# DWM1000_Base.net
KiCad netlist of a schematic drawn in Altium Designer
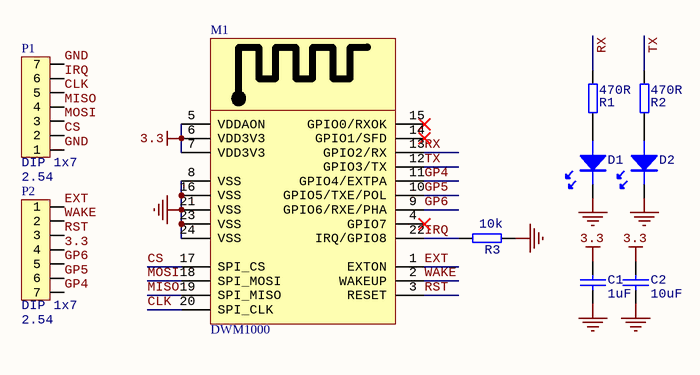
[diagram p0: DWM1000 Base.SchDoc]

(export (version "E")
  (design (tool "Eeschema 10.0.6"))
  (components
    (comp (ref "C1") (value "1uF") (footprint "0603C") (libsource (lib "HH_Lib_A") (part "CAP")))
    (comp (ref "C2") (value "10uF") (footprint "0603C") (libsource (lib "HH_Lib_A") (part "CAP")))
    (comp (ref "D1") (value "LED") (footprint "LED_0805B") (libsource (lib "HH_Lib_A") (part "LED")))
    (comp (ref "D2") (value "LED") (footprint "LED_0805R") (libsource (lib "HH_Lib_A") (part "LED")))
    (comp (ref "M1")
      (value "DWM1000")
      (footprint "HH_Pcb_B:DWM1000")
      (description "Module")
      (fields (field (name "MANUFACTURER") "Decawave Limited"))
      (libsource (lib "HH_Lib_B") (part "DWM1000"))
    )
    (comp (ref "P1")
      (value "2.54")
      (footprint "HDR1X7_2.54_180")
      (description "Header")
      (fields (field (name "TYPE") "DIP 1x7") (field (name "Comment") "DIP 1x7"))
      (libsource (lib "") (part "2.54MM_7P_1"))
    )
    (comp (ref "P2")
      (value "2.54")
      (footprint "HDR1X7_2.54_180")
      (description "Header")
      (fields (field (name "TYPE") "DIP 1x7") (field (name "Comment") "DIP 1x7"))
      (libsource (lib "HH_Lib_C") (part "2.54MM_7P"))
    )
    (comp (ref "R1") (value "470R") (footprint "0603R") (libsource (lib "HH_Lib_A") (part "RES")))
    (comp (ref "R2") (value "470R") (footprint "0603R") (libsource (lib "HH_Lib_A") (part "RES")))
    (comp (ref "R3") (value "10k") (footprint "0603R") (libsource (lib "HH_Lib_A") (part "RES")))
  )
  (nets
    (net (code "1") (name "/CLK") (class "Default")
      (node (ref "M1") (pin "20") (pinfunction "SPI_CLK_20") (pintype "passive"))
      (node (ref "P1") (pin "5") (pinfunction "5_5") (pintype "passive"))
    )
    (net (code "2") (name "/CS") (class "Default")
      (node (ref "M1") (pin "17") (pinfunction "SPI_CS_17") (pintype "passive"))
      (node (ref "P1") (pin "2") (pinfunction "2_2") (pintype "passive"))
    )
    (net (code "3") (name "/EXT") (class "Default")
      (node (ref "M1") (pin "1") (pinfunction "EXTON_1") (pintype "passive"))
      (node (ref "P2") (pin "1") (pinfunction "1_1") (pintype "passive"))
    )
    (net (code "4") (name "/GP4") (class "Default")
      (node (ref "M1") (pin "11") (pinfunction "GPIO4/EXTPA_11") (pintype "passive"))
      (node (ref "P2") (pin "7") (pinfunction "7_7") (pintype "passive"))
    )
    (net (code "5") (name "/GP5") (class "Default")
      (node (ref "M1") (pin "10") (pinfunction "GPIO5/TXE/POL_10") (pintype "passive"))
      (node (ref "P2") (pin "6") (pinfunction "6_6") (pintype "passive"))
    )
    (net (code "6") (name "/GP6") (class "Default")
      (node (ref "M1") (pin "9") (pinfunction "GPIO6/RXE/PHA_9") (pintype "passive"))
      (node (ref "P2") (pin "5") (pinfunction "5_5") (pintype "passive"))
    )
    (net (code "7") (name "/IRQ") (class "Default")
      (node (ref "M1") (pin "22") (pinfunction "IRQ/GPIO8_22") (pintype "passive"))
      (node (ref "P1") (pin "6") (pinfunction "6_6") (pintype "passive"))
      (node (ref "R3") (pin "2") (pinfunction "2_2") (pintype "passive"))
    )
    (net (code "8") (name "/MISO") (class "Default")
      (node (ref "M1") (pin "19") (pinfunction "SPI_MISO_19") (pintype "passive"))
      (node (ref "P1") (pin "4") (pinfunction "4_4") (pintype "passive"))
    )
    (net (code "9") (name "/MOSI") (class "Default")
      (node (ref "M1") (pin "18") (pinfunction "SPI_MOSI_18") (pintype "passive"))
      (node (ref "P1") (pin "3") (pinfunction "3_3") (pintype "passive"))
    )
    (net (code "10") (name "/RST") (class "Default")
      (node (ref "M1") (pin "3") (pinfunction "RESET_3") (pintype "passive"))
      (node (ref "P2") (pin "3") (pinfunction "3_3") (pintype "passive"))
    )
    (net (code "11") (name "/RX") (class "Default")
      (node (ref "M1") (pin "13") (pinfunction "GPIO2/RX_13") (pintype "passive"))
      (node (ref "R1") (pin "2") (pinfunction "2_2") (pintype "passive"))
    )
    (net (code "12") (name "/TX") (class "Default")
      (node (ref "M1") (pin "12") (pinfunction "GPIO3/TX_12") (pintype "passive"))
      (node (ref "R2") (pin "2") (pinfunction "2_2") (pintype "passive"))
    )
    (net (code "13") (name "/WAKE") (class "Default")
      (node (ref "M1") (pin "2") (pinfunction "WAKEUP_2") (pintype "passive"))
      (node (ref "P2") (pin "2") (pinfunction "2_2") (pintype "passive"))
    )
    (net (code "14") (name "3.3") (class "Default")
      (node (ref "C1") (pin "2") (pinfunction "2_2") (pintype "passive"))
      (node (ref "C2") (pin "2") (pinfunction "2_2") (pintype "passive"))
      (node (ref "M1") (pin "5") (pinfunction "VDDAON_5") (pintype "passive"))
      (node (ref "M1") (pin "6") (pinfunction "VDD3V3_6") (pintype "passive"))
      (node (ref "M1") (pin "7") (pinfunction "VDD3V3_7") (pintype "passive"))
      (node (ref "P2") (pin "4") (pinfunction "4_4") (pintype "passive"))
    )
    (net (code "15") (name "GND") (class "Default")
      (node (ref "C1") (pin "1") (pinfunction "1_1") (pintype "passive"))
      (node (ref "C2") (pin "1") (pinfunction "1_1") (pintype "passive"))
      (node (ref "D1") (pin "K") (pinfunction "K_K") (pintype "passive"))
      (node (ref "D2") (pin "K") (pinfunction "K_K") (pintype "passive"))
      (node (ref "M1") (pin "16") (pinfunction "VSS_16") (pintype "passive"))
      (node (ref "M1") (pin "21") (pinfunction "VSS_21") (pintype "passive"))
      (node (ref "M1") (pin "23") (pinfunction "VSS_23") (pintype "passive"))
      (node (ref "M1") (pin "24") (pinfunction "VSS_24") (pintype "passive"))
      (node (ref "M1") (pin "8") (pinfunction "VSS_8") (pintype "passive"))
      (node (ref "P1") (pin "1") (pinfunction "1_1") (pintype "passive"))
      (node (ref "P1") (pin "7") (pinfunction "7_7") (pintype "passive"))
      (node (ref "R3") (pin "1") (pinfunction "1_1") (pintype "passive"))
    )
    (net (code "16") (name "Net-(D1-PadA)") (class "Default")
      (node (ref "D1") (pin "A") (pinfunction "A_A") (pintype "passive"))
      (node (ref "R1") (pin "1") (pinfunction "1_1") (pintype "passive"))
    )
    (net (code "17") (name "Net-(D2-PadA)") (class "Default")
      (node (ref "D2") (pin "A") (pinfunction "A_A") (pintype "passive"))
      (node (ref "R2") (pin "1") (pinfunction "1_1") (pintype "passive"))
    )
    (net (code "18") (name "unconnected-(M1-GPIO0{slash}RXOK-Pad15)") (class "Default")
      (node (ref "M1") (pin "15") (pinfunction "GPIO0/RXOK_15") (pintype "passive+no_connect"))
    )
    (net (code "19") (name "unconnected-(M1-GPIO1{slash}SFD-Pad14)") (class "Default")
      (node (ref "M1") (pin "14") (pinfunction "GPIO1/SFD_14") (pintype "passive+no_connect"))
    )
    (net (code "20") (name "unconnected-(M1-GPIO7-Pad4)") (class "Default")
      (node (ref "M1") (pin "4") (pinfunction "GPIO7_4") (pintype "passive+no_connect"))
    )
  )
)
